# leds.net
KiCad netlist of a schematic drawn in Altium Designer
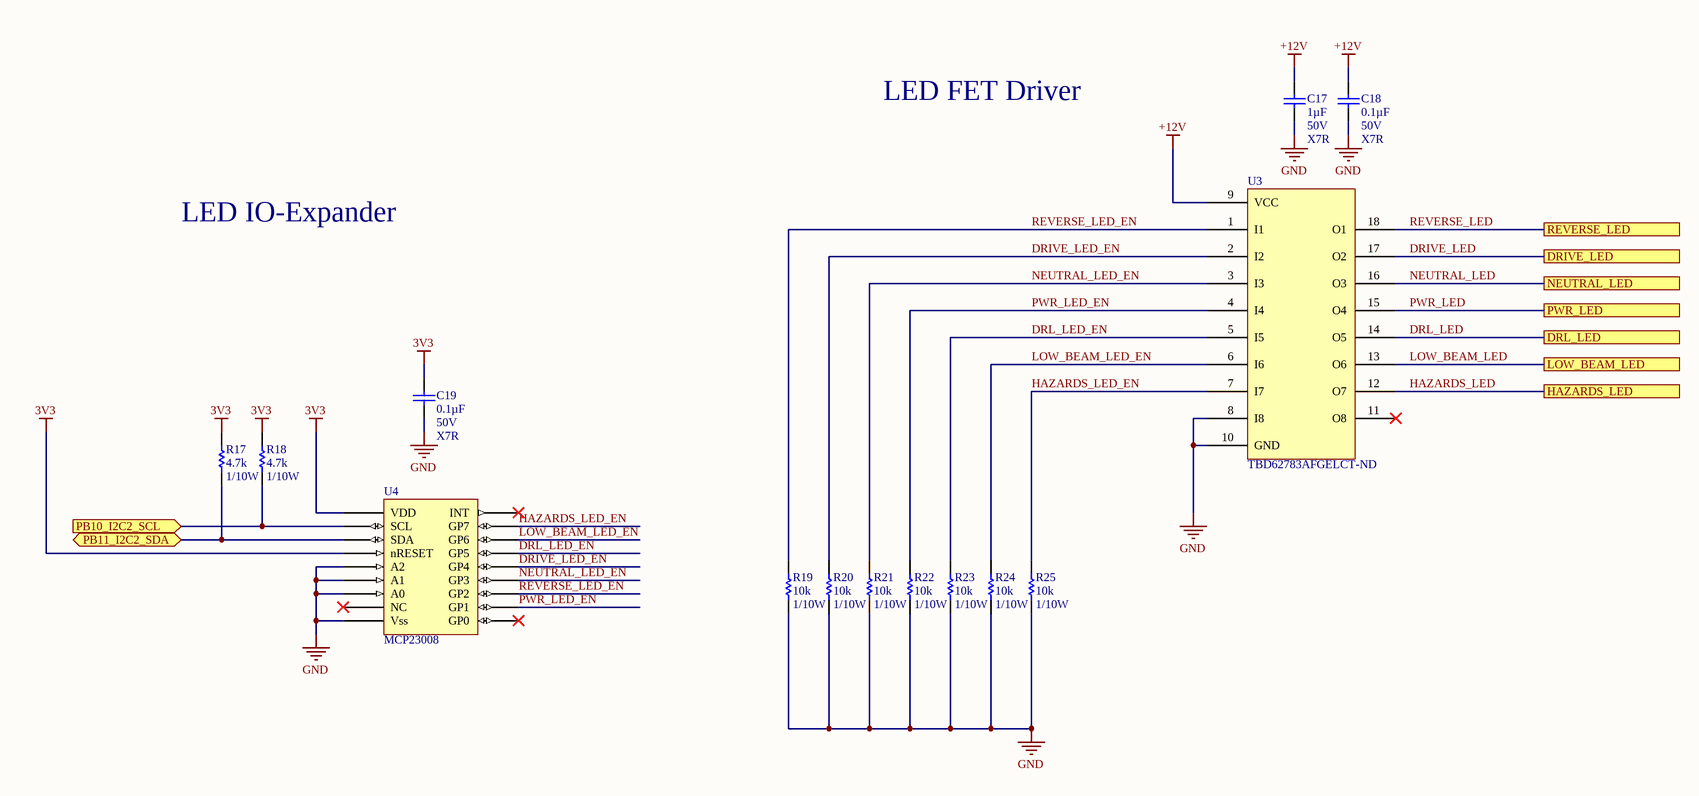
[diagram p0: leds.SchDoc]

(export (version "E")
  (design (tool "Eeschema 10.0.6"))
  (components
    (comp (ref "C17")
      (value "CAP CER 1UF 50V 10% X7R 0603")
      (footprint "CAP, 0603")
      (description "1µF ±10% 50V Ceramic Capacitor X7R 0603 (1608 Metric)")
      (fields
        (field (name "TOLERANCE") "±10%")
        (field (name "CAPACITANCE") "1µF")
        (field (name "VOLTAGE") "50V")
        (field (name "TEMPERATURE COEFFICIENT") "X7R")
      )
      (libsource (lib "Schematic Diagrams") (part "CAP CER 1UF 50V 10% X7R 0603"))
    )
    (comp (ref "C18")
      (value "CAP CER 0.1UF 50V 10% X7R 0603")
      (footprint "CAP, 0603")
      (description "0.10µF ±10% 50V Ceramic Capacitor X7R 0603 (1608 Metric)")
      (fields
        (field (name "TOLERANCE") "±10%")
        (field (name "CAPACITANCE") "0.1µF")
        (field (name "VOLTAGE") "50V")
        (field (name "TEMPERATURE COEFFICIENT") "X7R")
      )
      (libsource (lib "Schematic Diagrams") (part "CAP CER 0.1UF 50V 10% X7R 0603"))
    )
    (comp (ref "C19")
      (value "CAP CER 0.1UF 50V 10% X7R 0603")
      (footprint "CAP, 0603")
      (description "0.10µF ±10% 50V Ceramic Capacitor X7R 0603 (1608 Metric)")
      (fields
        (field (name "TOLERANCE") "±10%")
        (field (name "CAPACITANCE") "0.1µF")
        (field (name "VOLTAGE") "50V")
        (field (name "TEMPERATURE COEFFICIENT") "X7R")
      )
      (libsource (lib "Schematic Diagrams") (part "CAP CER 0.1UF 50V 10% X7R 0603"))
    )
    (comp (ref "R17")
      (value "RES 4.7K OHM 1% 1/10W 0603")
      (footprint "RES, 0603")
      (description "4.7k Ohm ±1% 0.1W, 1/10W Chip Resistor 0603 (1608 Metric) Moisture Resistant Thick Film")
      (fields
        (field (name "TOLERANCE") "±1%")
        (field (name "RESISTANCE (OHMS)") "4.7k")
        (field (name "POWER (WATTS)") "1/10W")
      )
      (libsource (lib "Schematic Diagrams") (part "RES 4.7K OHM 1% 1/10W 0603"))
    )
    (comp (ref "R18")
      (value "RES 4.7K OHM 1% 1/10W 0603")
      (footprint "RES, 0603")
      (description "4.7k Ohm ±1% 0.1W, 1/10W Chip Resistor 0603 (1608 Metric) Moisture Resistant Thick Film")
      (fields
        (field (name "TOLERANCE") "±1%")
        (field (name "RESISTANCE (OHMS)") "4.7k")
        (field (name "POWER (WATTS)") "1/10W")
      )
      (libsource (lib "Schematic Diagrams") (part "RES 4.7K OHM 1% 1/10W 0603"))
    )
    (comp (ref "R19")
      (value "RES 10K OHM 1% 1/10W 0603")
      (footprint "RES, 0603")
      (description "RES SMD 10K OHM 1% 1/10W 0603")
      (fields
        (field (name "TOLERANCE") "±1%")
        (field (name "RESISTANCE") "10k")
        (field (name "POWER") "1/10W")
      )
      (libsource (lib "Schematic Diagrams") (part "RES 10K OHM 1% 1/10W 0603"))
    )
    (comp (ref "R20")
      (value "RES 10K OHM 1% 1/10W 0603")
      (footprint "RES, 0603")
      (description "RES SMD 10K OHM 1% 1/10W 0603")
      (fields
        (field (name "TOLERANCE") "±1%")
        (field (name "RESISTANCE") "10k")
        (field (name "POWER") "1/10W")
      )
      (libsource (lib "Schematic Diagrams") (part "RES 10K OHM 1% 1/10W 0603"))
    )
    (comp (ref "R21")
      (value "RES 10K OHM 1% 1/10W 0603")
      (footprint "RES, 0603")
      (description "RES SMD 10K OHM 1% 1/10W 0603")
      (fields
        (field (name "TOLERANCE") "±1%")
        (field (name "RESISTANCE") "10k")
        (field (name "POWER") "1/10W")
      )
      (libsource (lib "Schematic Diagrams") (part "RES 10K OHM 1% 1/10W 0603"))
    )
    (comp (ref "R22")
      (value "RES 10K OHM 1% 1/10W 0603")
      (footprint "RES, 0603")
      (description "RES SMD 10K OHM 1% 1/10W 0603")
      (fields
        (field (name "TOLERANCE") "±1%")
        (field (name "RESISTANCE") "10k")
        (field (name "POWER") "1/10W")
      )
      (libsource (lib "Schematic Diagrams") (part "RES 10K OHM 1% 1/10W 0603"))
    )
    (comp (ref "R23")
      (value "RES 10K OHM 1% 1/10W 0603")
      (footprint "RES, 0603")
      (description "RES SMD 10K OHM 1% 1/10W 0603")
      (fields
        (field (name "TOLERANCE") "±1%")
        (field (name "RESISTANCE") "10k")
        (field (name "POWER") "1/10W")
      )
      (libsource (lib "Schematic Diagrams") (part "RES 10K OHM 1% 1/10W 0603"))
    )
    (comp (ref "R24")
      (value "RES 10K OHM 1% 1/10W 0603")
      (footprint "RES, 0603")
      (description "RES SMD 10K OHM 1% 1/10W 0603")
      (fields
        (field (name "TOLERANCE") "±1%")
        (field (name "RESISTANCE") "10k")
        (field (name "POWER") "1/10W")
      )
      (libsource (lib "Schematic Diagrams") (part "RES 10K OHM 1% 1/10W 0603"))
    )
    (comp (ref "R25")
      (value "RES 10K OHM 1% 1/10W 0603")
      (footprint "RES, 0603")
      (description "RES SMD 10K OHM 1% 1/10W 0603")
      (fields
        (field (name "TOLERANCE") "±1%")
        (field (name "RESISTANCE") "10k")
        (field (name "POWER") "1/10W")
      )
      (libsource (lib "Schematic Diagrams") (part "RES 10K OHM 1% 1/10W 0603"))
    )
    (comp (ref "U3")
      (value "IC LOAD SWITCH 8CH 0.5A 18SOP")
      (footprint "IC LOAD SWITCH 8CH 0.5A 18-SSOP")
      (description "IC LOAD SWITCH 8CHANNEL 0.5A 18SOP")
      (fields
        (field (name "MANUFACTURER") "Toshiba")
        (field (name "MANUFACTURER PART NUMBER") "TBD62783AFG,EL")
        (field (name "SUPPLIER PART NUMBER 1") "TBD62783AFGELCT-ND")
      )
      (libsource (lib "Schematic Diagrams") (part "IC LOAD SWITCH 8CH 0.5A 18SOP"))
    )
    (comp (ref "U4")
      (value "MCP23008")
      (footprint "IC 18SOIC")
      (description "MCP23008 I/O Expander 8B+1Int 18P SOIC")
      (fields
        (field (name "MANUFACTURER") "Microchip Technology")
        (field (name "MANUFACTURER PART NUMBER") "MCP23008T-E/SO")
      )
      (libsource (lib "Schematic Diagrams") (part "IC I/O EXPANDER I2C 8B 18SOIC"))
    )
  )
  (nets
    (net (code "1") (name "+12V") (class "Default")
      (node (ref "C17") (pin "1") (pinfunction "1_1") (pintype "passive"))
      (node (ref "C18") (pin "1") (pinfunction "1_1") (pintype "passive"))
      (node (ref "U3") (pin "9") (pinfunction "VCC_9") (pintype "passive"))
    )
    (net (code "2") (name "/DRIVE_LED") (class "Default")
      (node (ref "U3") (pin "17") (pinfunction "O2_17") (pintype "passive"))
    )
    (net (code "3") (name "/DRIVE_LED_EN") (class "Default")
      (node (ref "R20") (pin "1") (pinfunction "1_1") (pintype "passive"))
      (node (ref "U3") (pin "2") (pinfunction "I2_2") (pintype "passive"))
      (node (ref "U4") (pin "14") (pinfunction "GP4_14") (pintype "bidirectional"))
    )
    (net (code "4") (name "/DRL_LED") (class "Default")
      (node (ref "U3") (pin "14") (pinfunction "O5_14") (pintype "passive"))
    )
    (net (code "5") (name "/DRL_LED_EN") (class "Default")
      (node (ref "R23") (pin "1") (pinfunction "1_1") (pintype "passive"))
      (node (ref "U3") (pin "5") (pinfunction "I5_5") (pintype "passive"))
      (node (ref "U4") (pin "15") (pinfunction "GP5_15") (pintype "bidirectional"))
    )
    (net (code "6") (name "/HAZARDS_LED") (class "Default")
      (node (ref "U3") (pin "12") (pinfunction "O7_12") (pintype "passive"))
    )
    (net (code "7") (name "/HAZARDS_LED_EN") (class "Default")
      (node (ref "R25") (pin "1") (pinfunction "1_1") (pintype "passive"))
      (node (ref "U3") (pin "7") (pinfunction "I7_7") (pintype "passive"))
      (node (ref "U4") (pin "17") (pinfunction "GP7_17") (pintype "bidirectional"))
    )
    (net (code "8") (name "/LOW_BEAM_LED") (class "Default")
      (node (ref "U3") (pin "13") (pinfunction "O6_13") (pintype "passive"))
    )
    (net (code "9") (name "/LOW_BEAM_LED_EN") (class "Default")
      (node (ref "R24") (pin "1") (pinfunction "1_1") (pintype "passive"))
      (node (ref "U3") (pin "6") (pinfunction "I6_6") (pintype "passive"))
      (node (ref "U4") (pin "16") (pinfunction "GP6_16") (pintype "bidirectional"))
    )
    (net (code "10") (name "/NEUTRAL_LED") (class "Default")
      (node (ref "U3") (pin "16") (pinfunction "O3_16") (pintype "passive"))
    )
    (net (code "11") (name "/NEUTRAL_LED_EN") (class "Default")
      (node (ref "R21") (pin "1") (pinfunction "1_1") (pintype "passive"))
      (node (ref "U3") (pin "3") (pinfunction "I3_3") (pintype "passive"))
      (node (ref "U4") (pin "13") (pinfunction "GP3_13") (pintype "bidirectional"))
    )
    (net (code "12") (name "/PB10_I2C2_SCL") (class "Default")
      (node (ref "R18") (pin "2") (pinfunction "2_2") (pintype "passive"))
      (node (ref "U4") (pin "1") (pinfunction "SCL_1") (pintype "bidirectional"))
    )
    (net (code "13") (name "/PB11_I2C2_SDA") (class "Default")
      (node (ref "R17") (pin "2") (pinfunction "2_2") (pintype "passive"))
      (node (ref "U4") (pin "2") (pinfunction "SDA_2") (pintype "bidirectional"))
    )
    (net (code "14") (name "/PWR_LED") (class "Default")
      (node (ref "U3") (pin "15") (pinfunction "O4_15") (pintype "passive"))
    )
    (net (code "15") (name "/PWR_LED_EN") (class "Default")
      (node (ref "R22") (pin "1") (pinfunction "1_1") (pintype "passive"))
      (node (ref "U3") (pin "4") (pinfunction "I4_4") (pintype "passive"))
      (node (ref "U4") (pin "11") (pinfunction "GP1_11") (pintype "bidirectional"))
    )
    (net (code "16") (name "/REVERSE_LED") (class "Default")
      (node (ref "U3") (pin "18") (pinfunction "O1_18") (pintype "passive"))
    )
    (net (code "17") (name "/REVERSE_LED_EN") (class "Default")
      (node (ref "R19") (pin "1") (pinfunction "1_1") (pintype "passive"))
      (node (ref "U3") (pin "1") (pinfunction "I1_1") (pintype "passive"))
      (node (ref "U4") (pin "12") (pinfunction "GP2_12") (pintype "bidirectional"))
    )
    (net (code "18") (name "3V3") (class "Default")
      (node (ref "C19") (pin "1") (pinfunction "1_1") (pintype "passive"))
      (node (ref "R17") (pin "1") (pinfunction "1_1") (pintype "passive"))
      (node (ref "R18") (pin "1") (pinfunction "1_1") (pintype "passive"))
      (node (ref "U4") (pin "18") (pinfunction "VDD_18") (pintype "power_in"))
      (node (ref "U4") (pin "6") (pinfunction "nRESET_6") (pintype "input"))
    )
    (net (code "19") (name "GND") (class "Default")
      (node (ref "C17") (pin "2") (pinfunction "2_2") (pintype "passive"))
      (node (ref "C18") (pin "2") (pinfunction "2_2") (pintype "passive"))
      (node (ref "C19") (pin "2") (pinfunction "2_2") (pintype "passive"))
      (node (ref "R19") (pin "2") (pinfunction "2_2") (pintype "passive"))
      (node (ref "R20") (pin "2") (pinfunction "2_2") (pintype "passive"))
      (node (ref "R21") (pin "2") (pinfunction "2_2") (pintype "passive"))
      (node (ref "R22") (pin "2") (pinfunction "2_2") (pintype "passive"))
      (node (ref "R23") (pin "2") (pinfunction "2_2") (pintype "passive"))
      (node (ref "R24") (pin "2") (pinfunction "2_2") (pintype "passive"))
      (node (ref "R25") (pin "2") (pinfunction "2_2") (pintype "passive"))
      (node (ref "U3") (pin "10") (pinfunction "GND_10") (pintype "passive"))
      (node (ref "U3") (pin "8") (pinfunction "I8_8") (pintype "passive"))
      (node (ref "U4") (pin "3") (pinfunction "A2_3") (pintype "input"))
      (node (ref "U4") (pin "4") (pinfunction "A1_4") (pintype "input"))
      (node (ref "U4") (pin "5") (pinfunction "A0_5") (pintype "input"))
      (node (ref "U4") (pin "9") (pinfunction "Vss_9") (pintype "power_in"))
    )
    (net (code "20") (name "unconnected-(U3-O8-Pad11)") (class "Default")
      (node (ref "U3") (pin "11") (pinfunction "O8_11") (pintype "passive+no_connect"))
    )
    (net (code "21") (name "unconnected-(U4-GP0-Pad10)") (class "Default")
      (node (ref "U4") (pin "10") (pinfunction "GP0_10") (pintype "bidirectional+no_connect"))
    )
    (net (code "22") (name "unconnected-(U4-INT-Pad8)") (class "Default")
      (node (ref "U4") (pin "8") (pinfunction "INT_8") (pintype "output+no_connect"))
    )
    (net (code "23") (name "unconnected-(U4-NC-Pad7)") (class "Default")
      (node (ref "U4") (pin "7") (pinfunction "NC_7") (pintype "passive+no_connect"))
    )
  )
)
